# 02_Power_Supply.net
KiCad netlist of a schematic drawn in Altium Designer
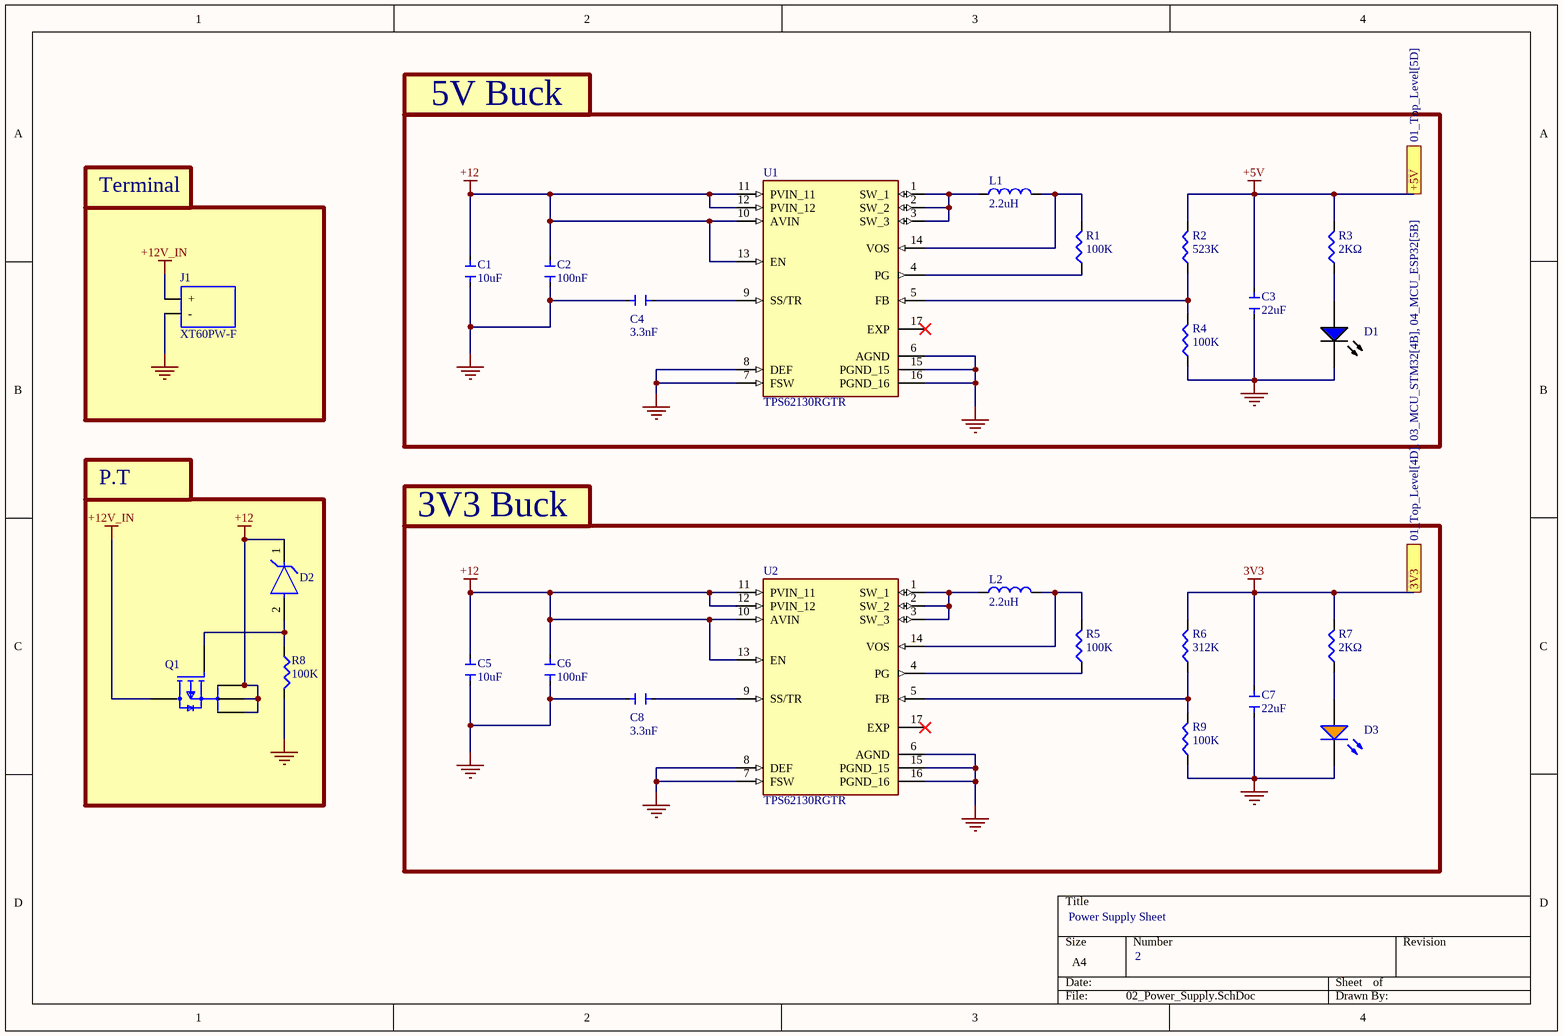
[diagram p0: 02_Power_Supply.SchDoc]

(export (version "E")
  (design (tool "Eeschema 10.0.6"))
  (components
    (comp (ref "C1")
      (value "10uF")
      (footprint "CAP_10uF")
      (description "CAP CER 10UF 10V X5R 0402")
      (fields
        (field (name "MANUFACTURER") "Samsung Electro-Mechanics")
        (field (name "MANUFACTURER PART NUMBER") "C307415")
      )
      (libsource (lib "Components_Schlib") (part "CAP_0402_10UF"))
    )
    (comp (ref "C2")
      (value "100nF")
      (footprint "CAP_100nF")
      (description "CAP 100nF 50V X7R ±10% 0603 Ceramic Capacitors RoHS")
      (fields
        (field (name "MANUFACTURER") "YAGEO")
        (field (name "MANUFACTURER PART NUMBER") "CC0603KRX7R9BB104")
      )
      (libsource (lib "Components_Schlib") (part "CAP_100nF"))
    )
    (comp (ref "C3")
      (value "22uF")
      (footprint "CAP_22uF")
      (description "CAP 22uF 25V X5R ±20% 0805 Ceramic Capacitors RoHS")
      (fields
        (field (name "MANUFACTURER") "Samsung Electro-Mechanics")
        (field (name "MANUFACTURER PART NUMBER") "CL21A226MAYNNNE")
      )
      (libsource (lib "Components_Schlib") (part "CAP_22uF"))
    )
    (comp (ref "C4")
      (value "3.3nF")
      (footprint "CAP_0603_0.33uF")
      (libsource (lib "Components_Schlib") (part "CAP_0603_0.33uF"))
    )
    (comp (ref "C5")
      (value "10uF")
      (footprint "CAP_10uF")
      (description "CAP CER 10UF 10V X5R 0402")
      (fields
        (field (name "MANUFACTURER") "Samsung Electro-Mechanics")
        (field (name "MANUFACTURER PART NUMBER") "C307415")
      )
      (libsource (lib "Components_Schlib") (part "CAP_0402_10UF"))
    )
    (comp (ref "C6")
      (value "100nF")
      (footprint "CAP_100nF")
      (description "CAP 100nF 50V X7R ±10% 0603 Ceramic Capacitors RoHS")
      (fields
        (field (name "MANUFACTURER") "YAGEO")
        (field (name "MANUFACTURER PART NUMBER") "CC0603KRX7R9BB104")
      )
      (libsource (lib "Components_Schlib") (part "CAP_100nF"))
    )
    (comp (ref "C7")
      (value "22uF")
      (footprint "CAP_22uF")
      (description "CAP 22uF 25V X5R ±20% 0805 Ceramic Capacitors RoHS")
      (fields
        (field (name "MANUFACTURER") "Samsung Electro-Mechanics")
        (field (name "MANUFACTURER PART NUMBER") "CL21A226MAYNNNE")
      )
      (libsource (lib "Components_Schlib") (part "CAP_22uF"))
    )
    (comp (ref "C8")
      (value "3.3nF")
      (footprint "CAP_0603_0.33uF")
      (libsource (lib "Components_Schlib") (part "CAP_0603_0.33uF"))
    )
    (comp (ref "D1")
      (value "HSMR-C190")
      (footprint "AVAG-HSMX-C190_V")
      (description "LED Uni-Color Blue, 78 mW, 20 mA, -40 to 85 degC, 2-Pin SMD, RoHS, Tape and Reel")
      (fields (field (name "POWER") "78mW") (field (name "MANUFACTURER") "Avago"))
      (libsource (lib "Youssef Adel") (part "LED-BLUE-AK-2"))
    )
    (comp (ref "D2")
      (value "SMAZ15-13-F")
      (footprint "FP-SMA-MFG")
      (description "DIODE ZENER 15V 1W SMA")
      (fields
        (field (name "MANUFACTURER") "Diodes")
        (field (name "OCTOPART") "https://octopart.com/smaz15-13-f-diodes+inc.-334038")
      )
      (libsource (lib "Altium Content Vault") (part "f813f71cba58e380607f5dd3caf9714"))
    )
    (comp (ref "D3")
      (value "HSMD-C190")
      (footprint "AVAG-HSMX-C190_V")
      (description "LED Uni-Color Orange, 52 mW, 20 mA, -40 to 85 degC, 2-Pin SMD, RoHS, Tape and Reel")
      (fields (field (name "MANUFACTURER") "Avago") (field (name "POWER") "52mW"))
      (libsource (lib "Youssef Adel") (part "LED-ORANGE-AK-2"))
    )
    (comp (ref "J1")
      (value "XT60PW-F")
      (footprint "XT60PW-F")
      (fields (field (name "MANUFACTURER") "Changzhou Amass Elec"))
      (libsource (lib "Youssef Adel") (part "XT60PW-M"))
    )
    (comp (ref "L1")
      (value "2.2uH")
      (footprint "IND_2.2uH")
      (description "2.2uH Magnetic Shielded Inductor 7A SMD,12.3x12.3mm Fixed Inductors RoHS")
      (libsource (lib "Components_Schlib") (part "IND_2.2uH"))
    )
    (comp (ref "L2")
      (value "2.2uH")
      (footprint "IND_2.2uH")
      (description "2.2uH Magnetic Shielded Inductor 7A SMD,12.3x12.3mm Fixed Inductors RoHS")
      (libsource (lib "Components_Schlib") (part "IND_2.2uH"))
    )
    (comp (ref "Q1")
      (value "SQJ431AEP-T1_GE3")
      (footprint "FP-S19-0643-SINGLE-MFG")
      (description "MOSFET P-CH 200V 9.4A PPAK SO-8")
      (libsource (lib "Altium Content Vault") (part "abcee65aa20a5edc4f753be34d9ba2d"))
    )
    (comp (ref "R1")
      (value "100K")
      (footprint "RES_100K")
      (description "100KΩ ±1% 0603 Thick Film Resistor")
      (libsource (lib "Components_Schlib") (part "RES_0603_100K"))
    )
    (comp (ref "R2")
      (value "523K")
      (footprint "RES_523K")
      (description "RES Thick Film, 523KΩ, 1%, 0.33W, 100ppm/°C, 0603")
      (fields (field (name "TOLERANCE") "1%"))
      (libsource (lib "Components_Schlib") (part "RES_0603_523K"))
    )
    (comp (ref "R3")
      (value "2KΩ")
      (footprint "RES_312K")
      (description "Fixed Resistor, Thin Film, 0.1W, 2K, 75V, 0.1% +/-Tol, 25ppm/Cel, Surface Mount, 0603")
      (fields
        (field (name "MANUFACTURER") "Yageo Group")
        (field (name "MANUFACTURER PART NUMBER") "RT0603BRD07383KL")
      )
      (libsource (lib "Components_Schlib") (part "RES_0603_312K"))
    )
    (comp (ref "R4")
      (value "100K")
      (footprint "RES_100K")
      (description "100KΩ ±1% 0603 Thick Film Resistor")
      (libsource (lib "Components_Schlib") (part "RES_0603_100K"))
    )
    (comp (ref "R5")
      (value "100K")
      (footprint "RES_100K")
      (description "100KΩ ±1% 0603 Thick Film Resistor")
      (libsource (lib "Components_Schlib") (part "RES_0603_100K"))
    )
    (comp (ref "R6")
      (value "312K")
      (footprint "RES_523K")
      (description "RES Thick Film, 312KΩ, 1%, 0.33W, 100ppm/°C, 0603")
      (fields (field (name "TOLERANCE") "1%"))
      (libsource (lib "Components_Schlib") (part "RES_0603_523K"))
    )
    (comp (ref "R7")
      (value "2KΩ")
      (footprint "RES_312K")
      (description "Fixed Resistor, Thin Film, 0.1W, 2K, 75V, 0.1% +/-Tol, 25ppm/Cel, Surface Mount, 0603")
      (fields
        (field (name "MANUFACTURER") "Yageo Group")
        (field (name "MANUFACTURER PART NUMBER") "RT0603BRD07383KL")
      )
      (libsource (lib "Components_Schlib") (part "RES_0603_312K"))
    )
    (comp (ref "R8")
      (value "100K")
      (footprint "RES_100K")
      (description "100KΩ ±1% 0603 Thick Film Resistor")
      (libsource (lib "Components_Schlib") (part "RES_0603_100K"))
    )
    (comp (ref "R9")
      (value "100K")
      (footprint "RES_100K")
      (description "100KΩ ±1% 0603 Thick Film Resistor")
      (libsource (lib "Components_Schlib") (part "RES_0603_100K"))
    )
    (comp (ref "U1")
      (value "TPS62130RGTR")
      (footprint "QFN50P300X300X100-17N")
      (description "3-17V 3A Step-Down Converter with DCS-Control in 3x3 QFN Package")
      (fields (field (name "MF") "Texas Instruments"))
      (libsource (lib "Components_Schlib") (part "TPS62130RGTR"))
    )
    (comp (ref "U2")
      (value "TPS62130RGTR")
      (footprint "QFN50P300X300X100-17N")
      (description "3-17V 3A Step-Down Converter with DCS-Control in 3x3 QFN Package")
      (fields (field (name "MF") "Texas Instruments"))
      (libsource (lib "Components_Schlib") (part "TPS62130RGTR"))
    )
  )
  (nets
    (net (code "1") (name "+5V") (class "Default")
      (node (ref "C3") (pin "2") (pinfunction "2_2") (pintype "passive"))
      (node (ref "R2") (pin "2") (pinfunction "2_2") (pintype "passive"))
      (node (ref "R3") (pin "2") (pinfunction "2_2") (pintype "passive"))
    )
    (net (code "2") (name "+12") (class "Default")
      (node (ref "C1") (pin "2") (pinfunction "2_2") (pintype "passive"))
      (node (ref "C2") (pin "2") (pinfunction "2_2") (pintype "passive"))
      (node (ref "C5") (pin "2") (pinfunction "2_2") (pintype "passive"))
      (node (ref "C6") (pin "2") (pinfunction "2_2") (pintype "passive"))
      (node (ref "D2") (pin "1") (pinfunction "C_1") (pintype "passive"))
      (node (ref "Q1") (pin "1") (pinfunction "S_1") (pintype "passive"))
      (node (ref "Q1") (pin "2") (pinfunction "S_2") (pintype "passive"))
      (node (ref "Q1") (pin "3") (pinfunction "S_3") (pintype "passive"))
      (node (ref "U1") (pin "10") (pinfunction "AVIN_10") (pintype "input"))
      (node (ref "U1") (pin "11") (pinfunction "PVIN_11_11") (pintype "input"))
      (node (ref "U1") (pin "12") (pinfunction "PVIN_12_12") (pintype "input"))
      (node (ref "U1") (pin "13") (pinfunction "EN_13") (pintype "input"))
      (node (ref "U2") (pin "10") (pinfunction "AVIN_10") (pintype "input"))
      (node (ref "U2") (pin "11") (pinfunction "PVIN_11_11") (pintype "input"))
      (node (ref "U2") (pin "12") (pinfunction "PVIN_12_12") (pintype "input"))
      (node (ref "U2") (pin "13") (pinfunction "EN_13") (pintype "input"))
    )
    (net (code "3") (name "+12V_IN") (class "Default")
      (node (ref "J1") (pin "1") (pinfunction "+_1") (pintype "passive"))
      (node (ref "Q1") (pin "5-6-7-8") (pinfunction "D_5-6-7-8") (pintype "passive"))
    )
    (net (code "4") (name "3V3") (class "Default")
      (node (ref "C7") (pin "2") (pinfunction "2_2") (pintype "passive"))
      (node (ref "R6") (pin "2") (pinfunction "2_2") (pintype "passive"))
      (node (ref "R7") (pin "2") (pinfunction "2_2") (pintype "passive"))
    )
    (net (code "5") (name "GND") (class "Default")
      (node (ref "C1") (pin "1") (pinfunction "1_1") (pintype "passive"))
      (node (ref "C2") (pin "1") (pinfunction "1_1") (pintype "passive"))
      (node (ref "C3") (pin "1") (pinfunction "1_1") (pintype "passive"))
      (node (ref "C4") (pin "2") (pinfunction "2_2") (pintype "passive"))
      (node (ref "C5") (pin "1") (pinfunction "1_1") (pintype "passive"))
      (node (ref "C6") (pin "1") (pinfunction "1_1") (pintype "passive"))
      (node (ref "C7") (pin "1") (pinfunction "1_1") (pintype "passive"))
      (node (ref "C8") (pin "2") (pinfunction "2_2") (pintype "passive"))
      (node (ref "D1") (pin "2") (pinfunction "K_2") (pintype "passive"))
      (node (ref "D3") (pin "2") (pinfunction "K_2") (pintype "passive"))
      (node (ref "J1") (pin "2") (pinfunction "-_2") (pintype "passive"))
      (node (ref "R4") (pin "1") (pinfunction "1_1") (pintype "passive"))
      (node (ref "R8") (pin "2") (pinfunction "2_2") (pintype "passive"))
      (node (ref "R9") (pin "1") (pinfunction "1_1") (pintype "passive"))
      (node (ref "U1") (pin "15") (pinfunction "PGND_15_15") (pintype "power_in"))
      (node (ref "U1") (pin "16") (pinfunction "PGND_16_16") (pintype "power_in"))
      (node (ref "U1") (pin "6") (pinfunction "AGND_6") (pintype "power_in"))
      (node (ref "U1") (pin "7") (pinfunction "FSW_7") (pintype "input"))
      (node (ref "U1") (pin "8") (pinfunction "DEF_8") (pintype "input"))
      (node (ref "U2") (pin "15") (pinfunction "PGND_15_15") (pintype "power_in"))
      (node (ref "U2") (pin "16") (pinfunction "PGND_16_16") (pintype "power_in"))
      (node (ref "U2") (pin "6") (pinfunction "AGND_6") (pintype "power_in"))
      (node (ref "U2") (pin "7") (pinfunction "FSW_7") (pintype "input"))
      (node (ref "U2") (pin "8") (pinfunction "DEF_8") (pintype "input"))
    )
    (net (code "6") (name "Net-(D1-A)") (class "Default")
      (node (ref "D1") (pin "1") (pinfunction "A_1") (pintype "passive"))
      (node (ref "R3") (pin "1") (pinfunction "1_1") (pintype "passive"))
    )
    (net (code "7") (name "Net-(D2-A)") (class "Default")
      (node (ref "D2") (pin "2") (pinfunction "A_2") (pintype "passive"))
      (node (ref "Q1") (pin "4") (pinfunction "G_4") (pintype "passive"))
      (node (ref "R8") (pin "1") (pinfunction "1_1") (pintype "passive"))
    )
    (net (code "8") (name "Net-(D3-A)") (class "Default")
      (node (ref "D3") (pin "1") (pinfunction "A_1") (pintype "passive"))
      (node (ref "R7") (pin "1") (pinfunction "1_1") (pintype "passive"))
    )
    (net (code "9") (name "Net-(U1-FB)") (class "Default")
      (node (ref "R2") (pin "1") (pinfunction "1_1") (pintype "passive"))
      (node (ref "R4") (pin "2") (pinfunction "2_2") (pintype "passive"))
      (node (ref "U1") (pin "5") (pinfunction "FB_5") (pintype "input"))
    )
    (net (code "10") (name "Net-(U1-PG)") (class "Default")
      (node (ref "R1") (pin "1") (pinfunction "1_1") (pintype "passive"))
      (node (ref "U1") (pin "4") (pinfunction "PG_4") (pintype "output"))
    )
    (net (code "11") (name "Net-(U1-SS{slash}TR)") (class "Default")
      (node (ref "C4") (pin "1") (pinfunction "1_1") (pintype "passive"))
      (node (ref "U1") (pin "9") (pinfunction "SS/TR_9") (pintype "input"))
    )
    (net (code "12") (name "Net-(U1-SW_1)") (class "Default")
      (node (ref "L1") (pin "1") (pinfunction "1_1") (pintype "passive"))
      (node (ref "U1") (pin "1") (pinfunction "SW_1_1") (pintype "bidirectional"))
      (node (ref "U1") (pin "2") (pinfunction "SW_2_2") (pintype "bidirectional"))
      (node (ref "U1") (pin "3") (pinfunction "SW_3_3") (pintype "bidirectional"))
    )
    (net (code "13") (name "Net-(U1-VOS)") (class "Default")
      (node (ref "L1") (pin "2") (pinfunction "2_2") (pintype "passive"))
      (node (ref "R1") (pin "2") (pinfunction "2_2") (pintype "passive"))
      (node (ref "U1") (pin "14") (pinfunction "VOS_14") (pintype "input"))
    )
    (net (code "14") (name "Net-(U2-FB)") (class "Default")
      (node (ref "R6") (pin "1") (pinfunction "1_1") (pintype "passive"))
      (node (ref "R9") (pin "2") (pinfunction "2_2") (pintype "passive"))
      (node (ref "U2") (pin "5") (pinfunction "FB_5") (pintype "input"))
    )
    (net (code "15") (name "Net-(U2-PG)") (class "Default")
      (node (ref "R5") (pin "1") (pinfunction "1_1") (pintype "passive"))
      (node (ref "U2") (pin "4") (pinfunction "PG_4") (pintype "output"))
    )
    (net (code "16") (name "Net-(U2-SS{slash}TR)") (class "Default")
      (node (ref "C8") (pin "1") (pinfunction "1_1") (pintype "passive"))
      (node (ref "U2") (pin "9") (pinfunction "SS/TR_9") (pintype "input"))
    )
    (net (code "17") (name "Net-(U2-SW_1)") (class "Default")
      (node (ref "L2") (pin "1") (pinfunction "1_1") (pintype "passive"))
      (node (ref "U2") (pin "1") (pinfunction "SW_1_1") (pintype "bidirectional"))
      (node (ref "U2") (pin "2") (pinfunction "SW_2_2") (pintype "bidirectional"))
      (node (ref "U2") (pin "3") (pinfunction "SW_3_3") (pintype "bidirectional"))
    )
    (net (code "18") (name "Net-(U2-VOS)") (class "Default")
      (node (ref "L2") (pin "2") (pinfunction "2_2") (pintype "passive"))
      (node (ref "R5") (pin "2") (pinfunction "2_2") (pintype "passive"))
      (node (ref "U2") (pin "14") (pinfunction "VOS_14") (pintype "input"))
    )
    (net (code "19") (name "unconnected-(U1-EXP-Pad17)") (class "Default")
      (node (ref "U1") (pin "17") (pinfunction "EXP_17") (pintype "power_in+no_connect"))
    )
    (net (code "20") (name "unconnected-(U2-EXP-Pad17)") (class "Default")
      (node (ref "U2") (pin "17") (pinfunction "EXP_17") (pintype "power_in+no_connect"))
    )
  )
)
